# MOSFET_PCB.net
KiCad netlist of a schematic drawn in EAGLE
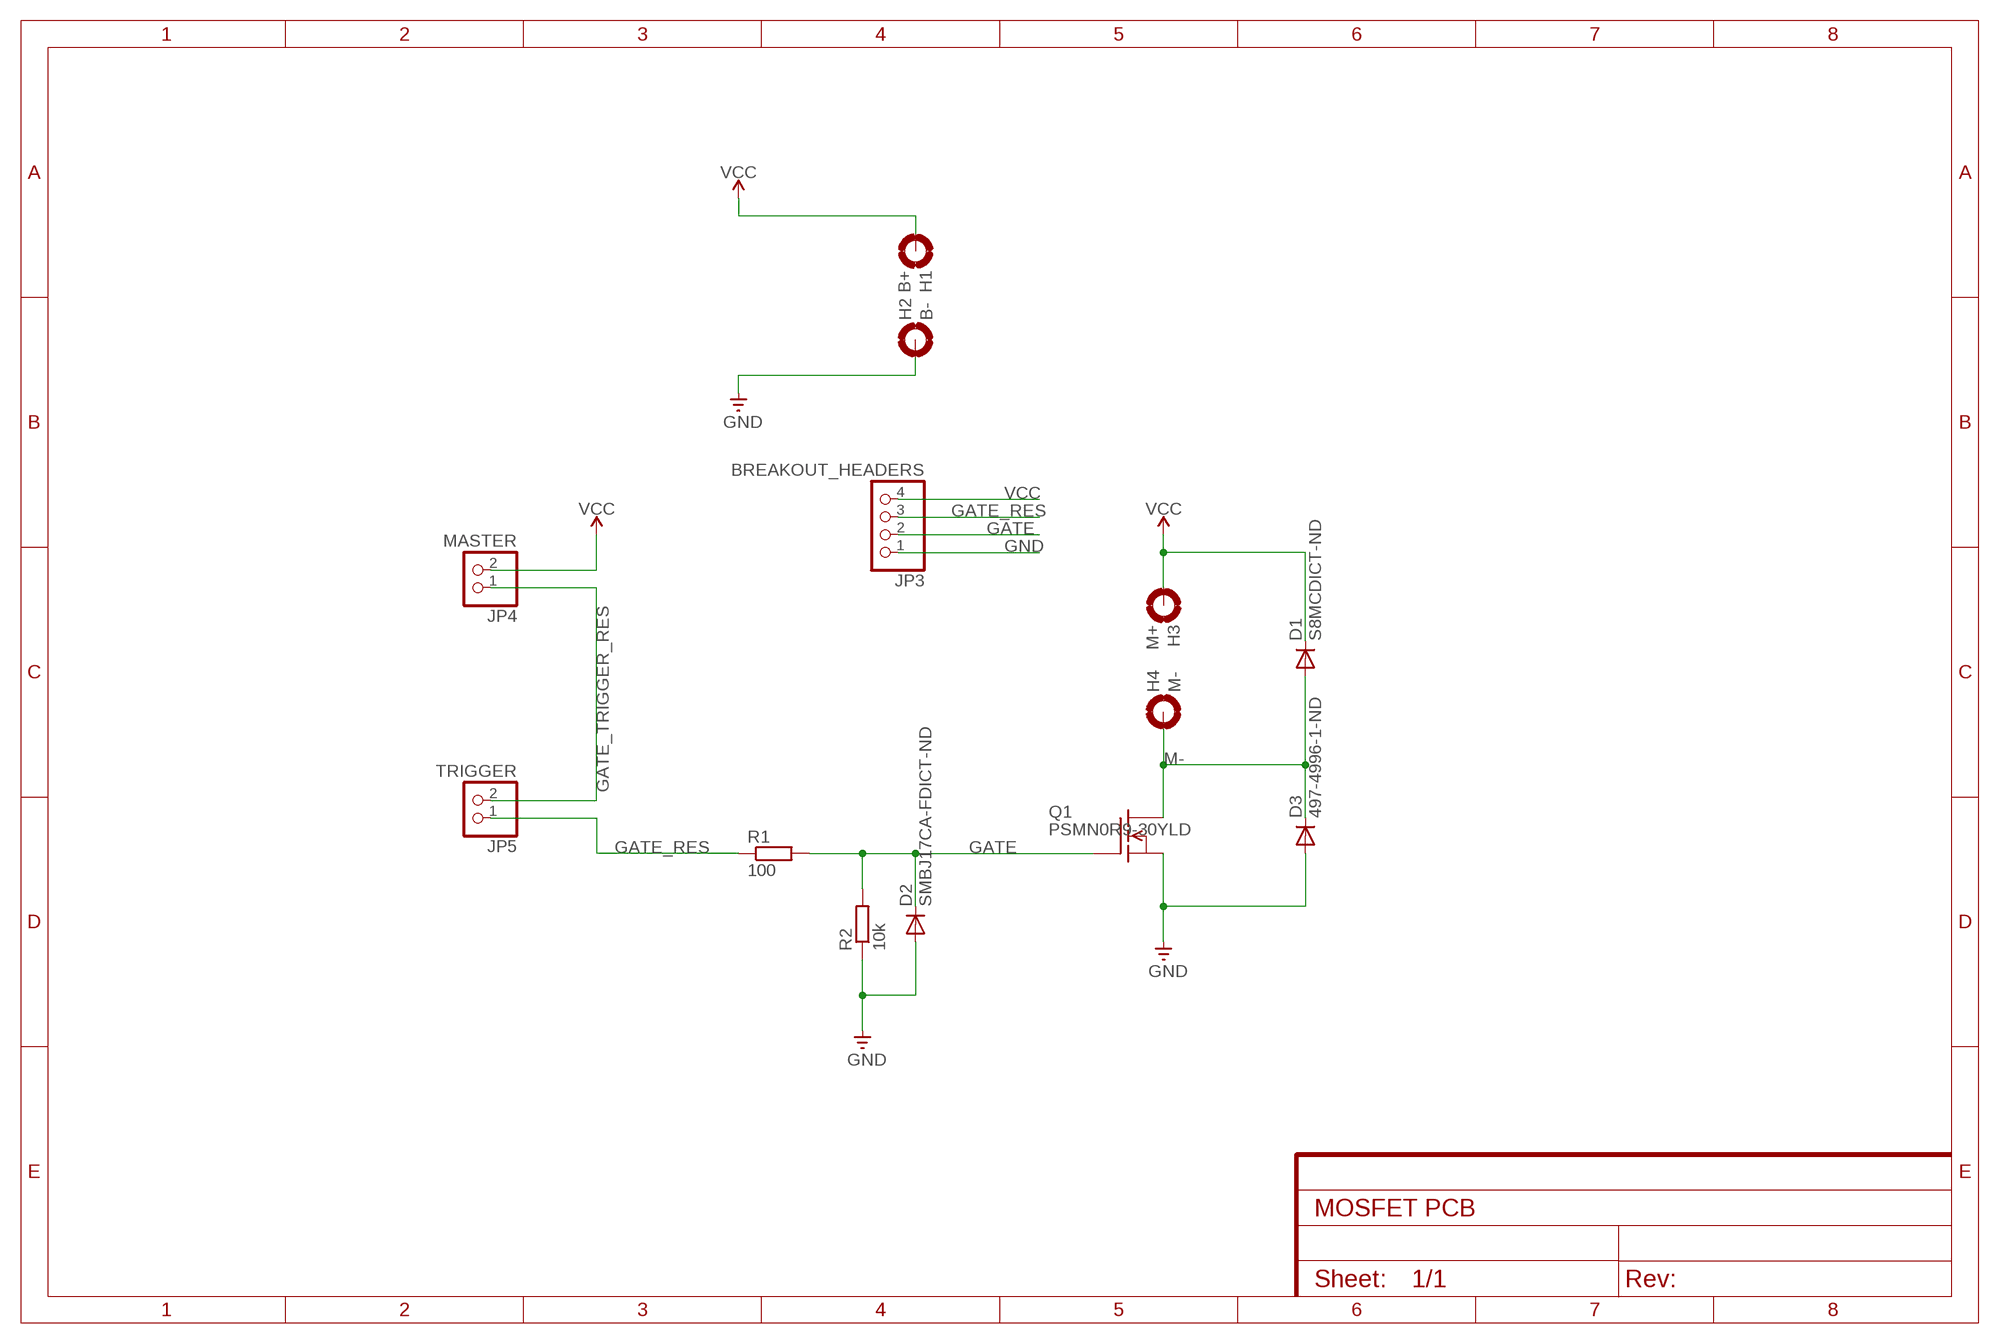
[diagram p0: schematic, sheet 1]

(export (version "E")
  (design (tool "Eeschema 10.0.6"))
  (components
    (comp (ref "D1")
      (value "S8MCDICT-ND")
      (footprint "eagle-import:DO214AB")
      (fields (field (name "MF") "Fairchild") (field (name "MPN") "S3A"))
      (libsource (lib "eagle-import") (part "S3A"))
    )
    (comp (ref "D2")
      (value "SMBJ17CA-FDICT-ND")
      (footprint "eagle-import:DO214AA")
      (fields (field (name "MF") "Fairchild") (field (name "MPN") "S2A"))
      (libsource (lib "eagle-import") (part "S2A"))
    )
    (comp (ref "D3")
      (value "497-4996-1-ND")
      (footprint "eagle-import:DO214AB")
      (fields (field (name "MF") "Fairchild") (field (name "MPN") "S3A"))
      (libsource (lib "eagle-import") (part "S3A"))
    )
    (comp (ref "H1")
      (value "B+")
      (footprint "eagle-import:MOUNT-HOLE-2.5MM")
      (libsource (lib "eagle-import") (part "MOUNT-HOLE-2.5MM"))
    )
    (comp (ref "H2")
      (value "B-")
      (footprint "eagle-import:MOUNT-HOLE-2.5MM")
      (libsource (lib "eagle-import") (part "MOUNT-HOLE-2.5MM"))
    )
    (comp (ref "H3")
      (value "M+")
      (footprint "eagle-import:MOUNT-HOLE-2.5MM")
      (libsource (lib "eagle-import") (part "MOUNT-HOLE-2.5MM"))
    )
    (comp (ref "H4")
      (value "M-")
      (footprint "eagle-import:MOUNT-HOLE-2.5MM")
      (libsource (lib "eagle-import") (part "MOUNT-HOLE-2.5MM"))
    )
    (comp (ref "JP3")
      (value "BREAKOUT_HEADERS")
      (footprint "eagle-import:1X04")
      (libsource (lib "eagle-import") (part "PINHD-1X4"))
    )
    (comp (ref "JP4")
      (value "MASTER")
      (footprint "eagle-import:1X02")
      (libsource (lib "eagle-import") (part "PINHD-1X2"))
    )
    (comp (ref "JP5")
      (value "TRIGGER")
      (footprint "eagle-import:1X02")
      (libsource (lib "eagle-import") (part "PINHD-1X2"))
    )
    (comp (ref "Q1")
      (value "PSMN0R9-30YLD")
      (footprint "eagle-import:LFPAK-EXTENDED-LEGS")
      (libsource (lib "eagle-import") (part "PSMN0R9-30YLD"))
    )
    (comp (ref "R1")
      (value "100")
      (footprint "eagle-import:R1206")
      (libsource (lib "eagle-import") (part "RR1206"))
    )
    (comp (ref "R2")
      (value "10k")
      (footprint "eagle-import:R1206")
      (libsource (lib "eagle-import") (part "RR1206"))
    )
  )
  (nets
    (net (code "1") (name "/GATE") (class "Default")
      (node (ref "D2") (pin "C") (pinfunction "C_C") (pintype "passive"))
      (node (ref "JP3") (pin "2") (pinfunction "2_2") (pintype "passive"))
      (node (ref "Q1") (pin "4") (pinfunction "G_4") (pintype "passive"))
      (node (ref "R1") (pin "2") (pinfunction "2_2") (pintype "passive"))
      (node (ref "R2") (pin "2") (pinfunction "2_2") (pintype "passive"))
    )
    (net (code "2") (name "/GATE_RES") (class "Default")
      (node (ref "JP3") (pin "3") (pinfunction "3_3") (pintype "passive"))
      (node (ref "JP5") (pin "1") (pinfunction "1_1") (pintype "passive"))
      (node (ref "R1") (pin "1") (pinfunction "1_1") (pintype "passive"))
    )
    (net (code "3") (name "/GATE_TRIGGER_RES") (class "Default")
      (node (ref "JP4") (pin "1") (pinfunction "1_1") (pintype "passive"))
      (node (ref "JP5") (pin "2") (pinfunction "2_2") (pintype "passive"))
    )
    (net (code "4") (name "/M-") (class "Default")
      (node (ref "D1") (pin "A") (pinfunction "A_A") (pintype "passive"))
      (node (ref "D3") (pin "C") (pinfunction "C_C") (pintype "passive"))
      (node (ref "H4") (pin "P$1") (pinfunction "MOUNT_P$1") (pintype "passive"))
      (node (ref "Q1") (pin "5") (pinfunction "D_5") (pintype "passive"))
    )
    (net (code "5") (name "GND") (class "Default")
      (node (ref "D2") (pin "A") (pinfunction "A_A") (pintype "passive"))
      (node (ref "D3") (pin "A") (pinfunction "A_A") (pintype "passive"))
      (node (ref "H2") (pin "P$1") (pinfunction "MOUNT_P$1") (pintype "passive"))
      (node (ref "JP3") (pin "1") (pinfunction "1_1") (pintype "passive"))
      (node (ref "Q1") (pin "1") (pinfunction "S_1") (pintype "passive"))
      (node (ref "Q1") (pin "2") (pinfunction "S_2") (pintype "passive"))
      (node (ref "Q1") (pin "3") (pinfunction "S_3") (pintype "passive"))
      (node (ref "R2") (pin "1") (pinfunction "1_1") (pintype "passive"))
    )
    (net (code "6") (name "VCC") (class "Default")
      (node (ref "D1") (pin "C") (pinfunction "C_C") (pintype "passive"))
      (node (ref "H1") (pin "P$1") (pinfunction "MOUNT_P$1") (pintype "passive"))
      (node (ref "H3") (pin "P$1") (pinfunction "MOUNT_P$1") (pintype "passive"))
      (node (ref "JP3") (pin "4") (pinfunction "4_4") (pintype "passive"))
      (node (ref "JP4") (pin "2") (pinfunction "2_2") (pintype "passive"))
    )
  )
)
